# BigLatchingRelay.net
KiCad netlist of a schematic drawn in EAGLE
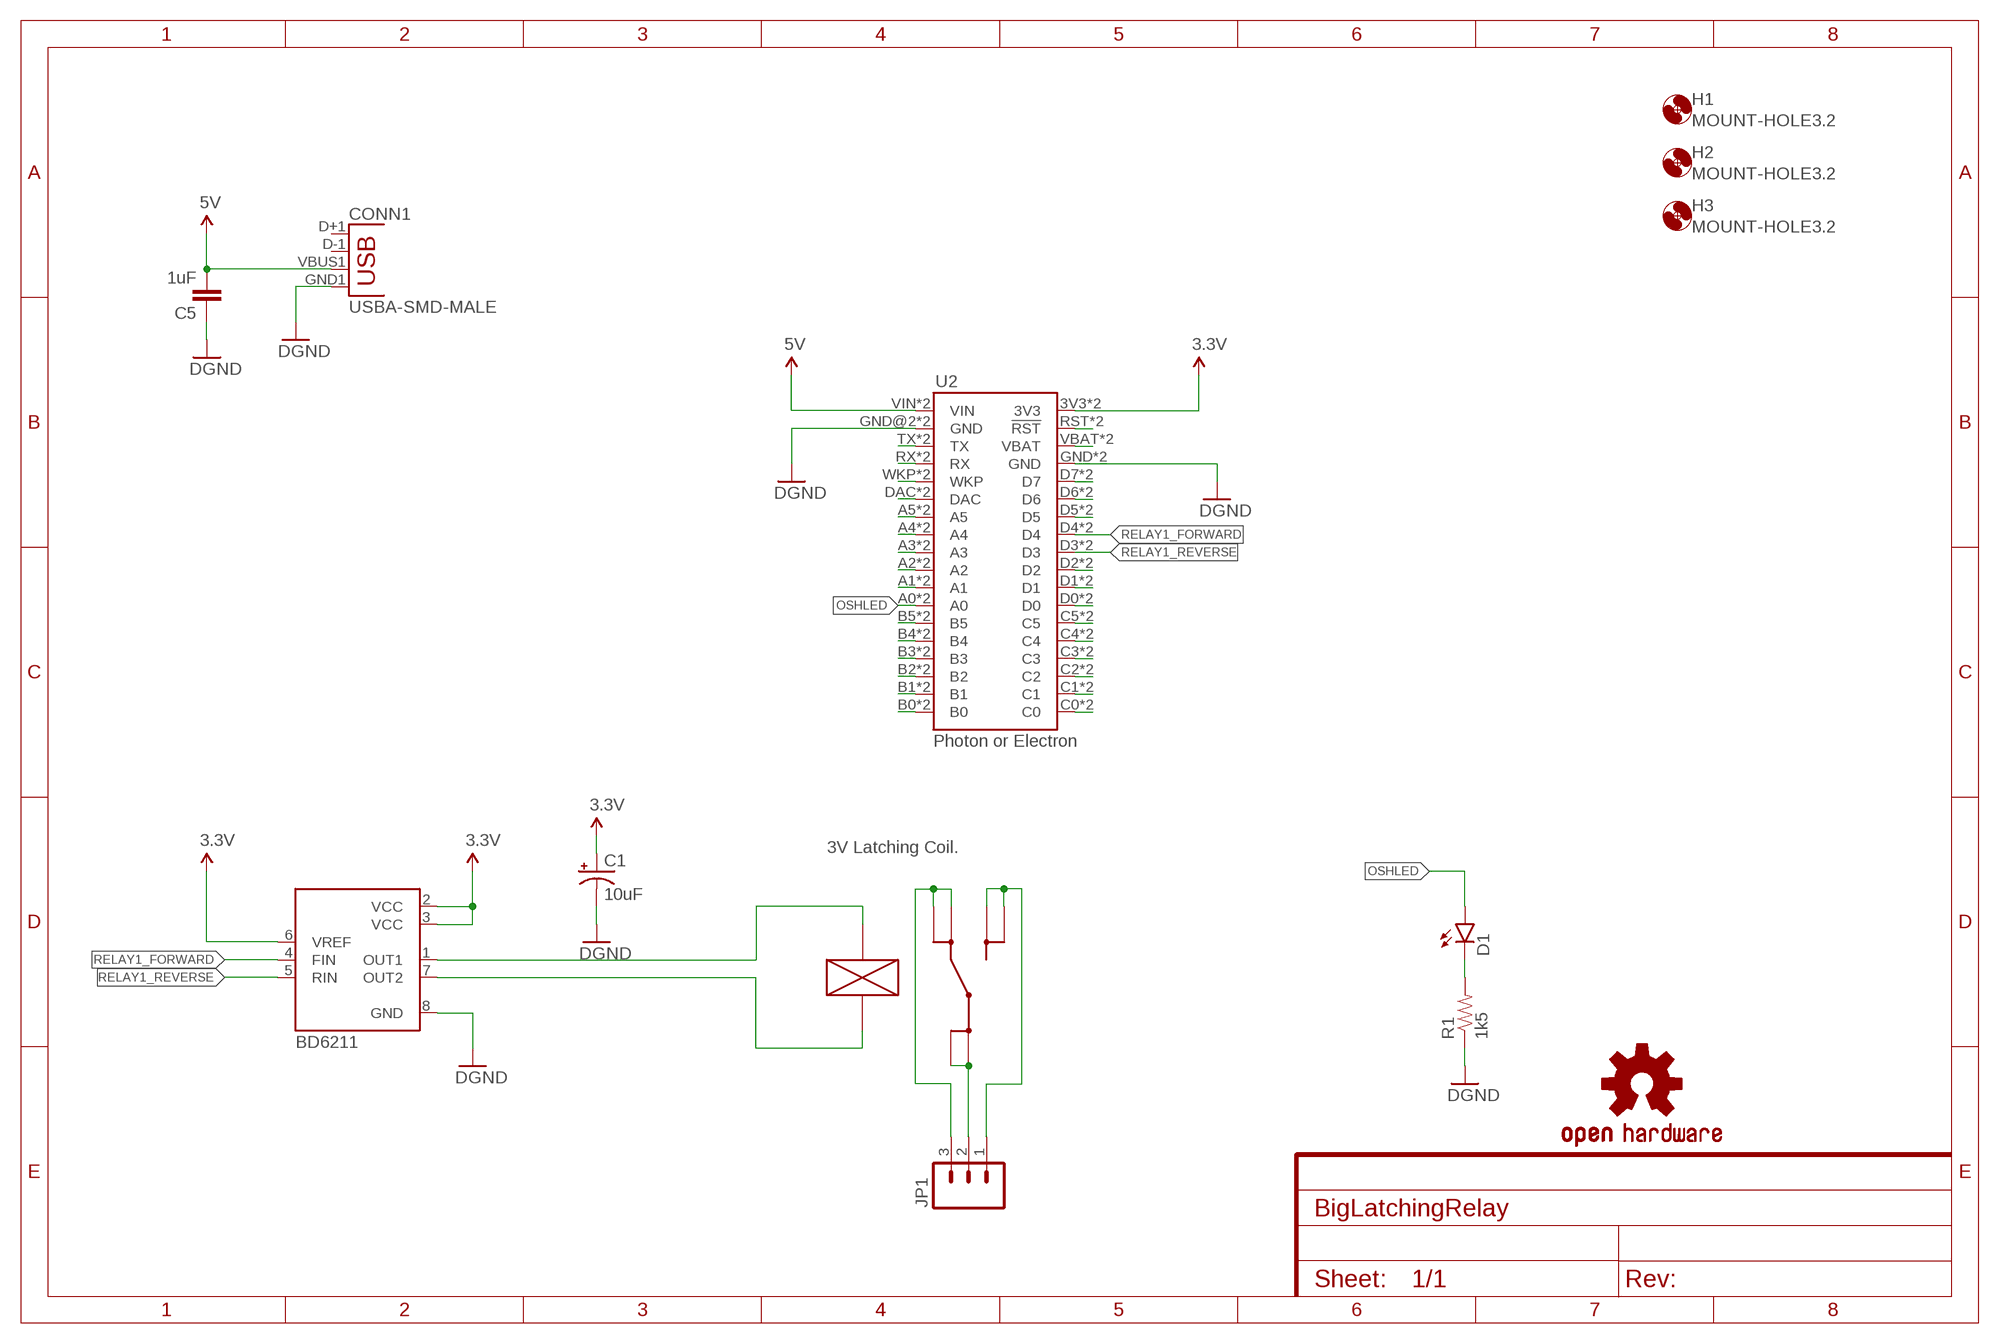
[diagram p0: schematic, sheet 1]

(export (version "E")
  (design (tool "Eeschema 10.0.6"))
  (components
    (comp (ref "C1")
      (value "10uF")
      (footprint "eagle-import:EIA3216")
      (libsource (lib "eagle-import") (part "10UF-16V-10%(TANT)"))
    )
    (comp (ref "C5")
      (value "1uF")
      (footprint "eagle-import:0805")
      (libsource (lib "eagle-import") (part "CAP0805"))
    )
    (comp (ref "CONN1")
      (value "USBA-SMD-MALE")
      (footprint "eagle-import:USB-A-SMT-MALE")
      (libsource (lib "eagle-import") (part "USBA-SMD-MALE"))
    )
    (comp (ref "D1")
      (value "LED1206-BOTTOM")
      (footprint "eagle-import:LED-1206-BOTTOM")
      (libsource (lib "eagle-import") (part "LED1206-BOTTOM"))
    )
    (comp (ref "H1")
      (value "MOUNT-HOLE3.2")
      (footprint "eagle-import:3,2")
      (libsource (lib "eagle-import") (part "MOUNT-HOLE3.2"))
    )
    (comp (ref "H2")
      (value "MOUNT-HOLE3.2")
      (footprint "eagle-import:3,2")
      (libsource (lib "eagle-import") (part "MOUNT-HOLE3.2"))
    )
    (comp (ref "H3")
      (value "MOUNT-HOLE3.2")
      (footprint "eagle-import:3,2")
      (libsource (lib "eagle-import") (part "MOUNT-HOLE3.2"))
    )
    (comp (ref "JP1")
      (value "M03-SCREW-5MM")
      (footprint "eagle-import:SCREWTERMINAL-5MM-3")
      (libsource (lib "eagle-import") (part "M03-SCREW-5MM"))
    )
    (comp (ref "LOGO1")
      (value "OSHW-LOGOM")
      (footprint "eagle-import:OSHW-LOGO-M")
      (libsource (lib "eagle-import") (part "OSHW-LOGOM"))
    )
    (comp (ref "R1")
      (value "1k5")
      (footprint "eagle-import:1206")
      (libsource (lib "eagle-import") (part "RESISTOR1206"))
    )
    (comp (ref "U$1")
      (value "RELAY_G5RL-1E")
      (footprint "eagle-import:G5RL-1E")
      (libsource (lib "eagle-import") (part "RELAY_G5RL-1E"))
    )
    (comp (ref "U2")
      (value "ELECTRONDUALNAMED")
      (footprint "eagle-import:ELECTRON_SIMPLE_SILK_NAMES_DUAL")
      (libsource (lib "eagle-import") (part "ELECTRONDUALNAMED"))
    )
    (comp (ref "U3")
      (value "BD6211F")
      (footprint "eagle-import:SOP8")
      (libsource (lib "eagle-import") (part "BD6211F"))
    )
  )
  (nets
    (net (code "1") (name "3.3V") (class "Default")
      (node (ref "C1") (pin "A") (pinfunction "+_A") (pintype "passive"))
      (node (ref "U2") (pin "3V3") (pinfunction "3V3_3V3") (pintype "power_in"))
      (node (ref "U2") (pin "3V3_1") (pinfunction "3V3_3V3_1") (pintype "power_in"))
      (node (ref "U3") (pin "2") (pinfunction "VCC_2") (pintype "power_in"))
      (node (ref "U3") (pin "3") (pinfunction "VCC_3") (pintype "power_in"))
      (node (ref "U3") (pin "6") (pinfunction "VREF_6") (pintype "passive"))
    )
    (net (code "2") (name "5V") (class "Default")
      (node (ref "C5") (pin "2") (pinfunction "2_2") (pintype "passive"))
      (node (ref "CONN1") (pin "VBUS1") (pinfunction "VBUS_VBUS1") (pintype "bidirectional"))
      (node (ref "U2") (pin "VIN") (pinfunction "VIN_VIN") (pintype "power_in"))
      (node (ref "U2") (pin "VIN_1B") (pinfunction "VIN_VIN_1B") (pintype "power_in"))
    )
    (net (code "3") (name "DGND") (class "Default")
      (node (ref "C1") (pin "C") (pinfunction "-_C") (pintype "passive"))
      (node (ref "C5") (pin "1") (pinfunction "1_1") (pintype "passive"))
      (node (ref "CONN1") (pin "GND1") (pinfunction "GND_GND1") (pintype "bidirectional"))
      (node (ref "R1") (pin "1") (pinfunction "1_1") (pintype "passive"))
      (node (ref "U2") (pin "GND") (pinfunction "GND_GND") (pintype "power_in"))
      (node (ref "U2") (pin "GND@2") (pinfunction "GND_GND@2") (pintype "power_in"))
      (node (ref "U2") (pin "GND_1") (pinfunction "GND_GND_1") (pintype "power_in"))
      (node (ref "U2") (pin "GND_1B") (pinfunction "GND_GND_1B") (pintype "power_in"))
      (node (ref "U3") (pin "8") (pinfunction "GND_8") (pintype "power_in"))
    )
    (net (code "4") (name "Net-(D1-PadC)") (class "Default")
      (node (ref "D1") (pin "C") (pinfunction "C_C") (pintype "passive"))
      (node (ref "R1") (pin "2") (pinfunction "2_2") (pintype "passive"))
    )
    (net (code "5") (name "Net-(JP1-Pad1)") (class "Default")
      (node (ref "JP1") (pin "1") (pinfunction "1_1") (pintype "passive"))
      (node (ref "U$1") (pin "NO@1") (pinfunction "NO_NO@1") (pintype "bidirectional"))
      (node (ref "U$1") (pin "NO@2") (pinfunction "NO_NO@2") (pintype "bidirectional"))
    )
    (net (code "6") (name "Net-(JP1-Pad2)") (class "Default")
      (node (ref "JP1") (pin "2") (pinfunction "2_2") (pintype "passive"))
      (node (ref "U$1") (pin "COM@1") (pinfunction "COM_COM@1") (pintype "bidirectional"))
      (node (ref "U$1") (pin "COM@2") (pinfunction "COM_COM@2") (pintype "bidirectional"))
    )
    (net (code "7") (name "Net-(JP1-Pad3)") (class "Default")
      (node (ref "JP1") (pin "3") (pinfunction "3_3") (pintype "passive"))
      (node (ref "U$1") (pin "NC@1") (pinfunction "NC_NC@1") (pintype "bidirectional"))
      (node (ref "U$1") (pin "NC@2") (pinfunction "NC_NC@2") (pintype "bidirectional"))
    )
    (net (code "8") (name "Net-(U2-A1-PadA1_1)") (class "Default")
      (node (ref "U2") (pin "A1") (pinfunction "A1_A1") (pintype "bidirectional"))
      (node (ref "U2") (pin "A1_1") (pinfunction "A1_A1_1") (pintype "bidirectional"))
    )
    (net (code "9") (name "Net-(U2-A2-PadA2_1)") (class "Default")
      (node (ref "U2") (pin "A2") (pinfunction "A2_A2") (pintype "bidirectional"))
      (node (ref "U2") (pin "A2_1") (pinfunction "A2_A2_1") (pintype "bidirectional"))
    )
    (net (code "10") (name "Net-(U2-A3-PadA3_1)") (class "Default")
      (node (ref "U2") (pin "A3") (pinfunction "A3_A3") (pintype "bidirectional"))
      (node (ref "U2") (pin "A3_1") (pinfunction "A3_A3_1") (pintype "bidirectional"))
    )
    (net (code "11") (name "Net-(U2-A4-PadA4_1)") (class "Default")
      (node (ref "U2") (pin "A4") (pinfunction "A4_A4") (pintype "bidirectional"))
      (node (ref "U2") (pin "A4_1") (pinfunction "A4_A4_1") (pintype "bidirectional"))
    )
    (net (code "12") (name "Net-(U2-A5-PadA5_1)") (class "Default")
      (node (ref "U2") (pin "A5") (pinfunction "A5_A5") (pintype "bidirectional"))
      (node (ref "U2") (pin "A5_1") (pinfunction "A5_A5_1") (pintype "bidirectional"))
    )
    (net (code "13") (name "Net-(U2-B0-PadB0_1)") (class "Default")
      (node (ref "U2") (pin "B0") (pinfunction "B0_B0") (pintype "bidirectional"))
      (node (ref "U2") (pin "B0_1") (pinfunction "B0_B0_1") (pintype "bidirectional"))
    )
    (net (code "14") (name "Net-(U2-B1-PadB1_1)") (class "Default")
      (node (ref "U2") (pin "B1") (pinfunction "B1_B1") (pintype "bidirectional"))
      (node (ref "U2") (pin "B1_1") (pinfunction "B1_B1_1") (pintype "bidirectional"))
    )
    (net (code "15") (name "Net-(U2-B2-PadB2_1)") (class "Default")
      (node (ref "U2") (pin "B2") (pinfunction "B2_B2") (pintype "bidirectional"))
      (node (ref "U2") (pin "B2_1") (pinfunction "B2_B2_1") (pintype "bidirectional"))
    )
    (net (code "16") (name "Net-(U2-B3-PadB3_1)") (class "Default")
      (node (ref "U2") (pin "B3") (pinfunction "B3_B3") (pintype "bidirectional"))
      (node (ref "U2") (pin "B3_1") (pinfunction "B3_B3_1") (pintype "bidirectional"))
    )
    (net (code "17") (name "Net-(U2-B4-PadB4_1)") (class "Default")
      (node (ref "U2") (pin "B4") (pinfunction "B4_B4") (pintype "bidirectional"))
      (node (ref "U2") (pin "B4_1") (pinfunction "B4_B4_1") (pintype "bidirectional"))
    )
    (net (code "18") (name "Net-(U2-B5-PadB5_1)") (class "Default")
      (node (ref "U2") (pin "B5") (pinfunction "B5_B5") (pintype "bidirectional"))
      (node (ref "U2") (pin "B5_1") (pinfunction "B5_B5_1") (pintype "bidirectional"))
    )
    (net (code "19") (name "Net-(U2-C0-PadC0_1)") (class "Default")
      (node (ref "U2") (pin "C0") (pinfunction "C0_C0") (pintype "bidirectional"))
      (node (ref "U2") (pin "C0_1") (pinfunction "C0_C0_1") (pintype "bidirectional"))
    )
    (net (code "20") (name "Net-(U2-C1-PadC1_1)") (class "Default")
      (node (ref "U2") (pin "C1") (pinfunction "C1_C1") (pintype "bidirectional"))
      (node (ref "U2") (pin "C1_1") (pinfunction "C1_C1_1") (pintype "bidirectional"))
    )
    (net (code "21") (name "Net-(U2-C2-PadC2_1)") (class "Default")
      (node (ref "U2") (pin "C2") (pinfunction "C2_C2") (pintype "bidirectional"))
      (node (ref "U2") (pin "C2_1") (pinfunction "C2_C2_1") (pintype "bidirectional"))
    )
    (net (code "22") (name "Net-(U2-C3-PadC3_1)") (class "Default")
      (node (ref "U2") (pin "C3") (pinfunction "C3_C3") (pintype "bidirectional"))
      (node (ref "U2") (pin "C3_1") (pinfunction "C3_C3_1") (pintype "bidirectional"))
    )
    (net (code "23") (name "Net-(U2-C4-PadC4_1)") (class "Default")
      (node (ref "U2") (pin "C4") (pinfunction "C4_C4") (pintype "bidirectional"))
      (node (ref "U2") (pin "C4_1") (pinfunction "C4_C4_1") (pintype "bidirectional"))
    )
    (net (code "24") (name "Net-(U2-C5-PadC5_1)") (class "Default")
      (node (ref "U2") (pin "C5") (pinfunction "C5_C5") (pintype "bidirectional"))
      (node (ref "U2") (pin "C5_1") (pinfunction "C5_C5_1") (pintype "bidirectional"))
    )
    (net (code "25") (name "Net-(U2-D0-PadD0_1)") (class "Default")
      (node (ref "U2") (pin "D0") (pinfunction "D0_D0") (pintype "bidirectional"))
      (node (ref "U2") (pin "D0_1") (pinfunction "D0_D0_1") (pintype "bidirectional"))
    )
    (net (code "26") (name "Net-(U2-D1-PadD1_1)") (class "Default")
      (node (ref "U2") (pin "D1") (pinfunction "D1_D1") (pintype "bidirectional"))
      (node (ref "U2") (pin "D1_1") (pinfunction "D1_D1_1") (pintype "bidirectional"))
    )
    (net (code "27") (name "Net-(U2-D2-PadD2_1)") (class "Default")
      (node (ref "U2") (pin "D2") (pinfunction "D2_D2") (pintype "bidirectional"))
      (node (ref "U2") (pin "D2_1") (pinfunction "D2_D2_1") (pintype "bidirectional"))
    )
    (net (code "28") (name "Net-(U2-D5-PadD5_1)") (class "Default")
      (node (ref "U2") (pin "D5") (pinfunction "D5_D5") (pintype "bidirectional"))
      (node (ref "U2") (pin "D5_1") (pinfunction "D5_D5_1") (pintype "bidirectional"))
    )
    (net (code "29") (name "Net-(U2-D6-PadD6_1)") (class "Default")
      (node (ref "U2") (pin "D6") (pinfunction "D6_D6") (pintype "bidirectional"))
      (node (ref "U2") (pin "D6_1") (pinfunction "D6_D6_1") (pintype "bidirectional"))
    )
    (net (code "30") (name "Net-(U2-D7-PadD7_1)") (class "Default")
      (node (ref "U2") (pin "D7") (pinfunction "D7_D7") (pintype "bidirectional"))
      (node (ref "U2") (pin "D7_1") (pinfunction "D7_D7_1") (pintype "bidirectional"))
    )
    (net (code "31") (name "Net-(U2-DAC-PadDAC_1)") (class "Default")
      (node (ref "U2") (pin "DAC") (pinfunction "DAC_DAC") (pintype "bidirectional"))
      (node (ref "U2") (pin "DAC_1") (pinfunction "DAC_DAC_1") (pintype "bidirectional"))
    )
    (net (code "32") (name "Net-(U2-PadRX)") (class "Default")
      (node (ref "U2") (pin "RX") (pinfunction "RX_RX") (pintype "bidirectional"))
      (node (ref "U2") (pin "RX_1") (pinfunction "RX_RX_1") (pintype "bidirectional"))
    )
    (net (code "33") (name "Net-(U2-PadTX)") (class "Default")
      (node (ref "U2") (pin "TX") (pinfunction "TX_TX") (pintype "bidirectional"))
      (node (ref "U2") (pin "TX_1") (pinfunction "TX_TX_1") (pintype "bidirectional"))
    )
    (net (code "34") (name "Net-(U2-PadVBAT)") (class "Default")
      (node (ref "U2") (pin "VBAT") (pinfunction "VBAT_VBAT") (pintype "passive"))
      (node (ref "U2") (pin "VBATT_1") (pinfunction "VBAT_VBATT_1") (pintype "passive"))
    )
    (net (code "35") (name "Net-(U2-PadWKP)") (class "Default")
      (node (ref "U2") (pin "WKP") (pinfunction "WKP_WKP") (pintype "bidirectional"))
      (node (ref "U2") (pin "WKP_1") (pinfunction "WKP_WKP_1") (pintype "bidirectional"))
    )
    (net (code "36") (name "Net-(U2-~{RST}-PadRST)") (class "Default")
      (node (ref "U2") (pin "RST") (pinfunction "~{RST}_RST") (pintype "bidirectional"))
      (node (ref "U2") (pin "RST_1") (pinfunction "~{RST}_RST_1") (pintype "bidirectional"))
    )
    (net (code "37") (name "Net-(U3-OUT1)") (class "Default")
      (node (ref "U$1") (pin "COIL+") (pinfunction "COIL+_COIL+") (pintype "bidirectional"))
      (node (ref "U3") (pin "1") (pinfunction "OUT1_1") (pintype "output"))
    )
    (net (code "38") (name "Net-(U3-OUT2)") (class "Default")
      (node (ref "U$1") (pin "COIL-") (pinfunction "COIL-_COIL-") (pintype "bidirectional"))
      (node (ref "U3") (pin "7") (pinfunction "OUT2_7") (pintype "output"))
    )
    (net (code "39") (name "OSHLED") (class "Default")
      (node (ref "D1") (pin "A") (pinfunction "A_A") (pintype "passive"))
      (node (ref "U2") (pin "A0") (pinfunction "A0_A0") (pintype "bidirectional"))
      (node (ref "U2") (pin "A0_1") (pinfunction "A0_A0_1") (pintype "bidirectional"))
    )
    (net (code "40") (name "RELAY1_FORWARD") (class "Default")
      (node (ref "U2") (pin "D4") (pinfunction "D4_D4") (pintype "bidirectional"))
      (node (ref "U2") (pin "D4_1") (pinfunction "D4_D4_1") (pintype "bidirectional"))
      (node (ref "U3") (pin "4") (pinfunction "FIN_4") (pintype "input"))
    )
    (net (code "41") (name "RELAY1_REVERSE") (class "Default")
      (node (ref "U2") (pin "D3") (pinfunction "D3_D3") (pintype "bidirectional"))
      (node (ref "U2") (pin "D3_1") (pinfunction "D3_D3_1") (pintype "bidirectional"))
      (node (ref "U3") (pin "5") (pinfunction "RIN_5") (pintype "input"))
    )
    (net (code "42") (name "unconnected-(CONN1-D+-PadD+1)") (class "Default")
      (node (ref "CONN1") (pin "D+1") (pinfunction "D+_D+1") (pintype "bidirectional"))
    )
    (net (code "43") (name "unconnected-(CONN1-D--PadD-1)") (class "Default")
      (node (ref "CONN1") (pin "D-1") (pinfunction "D-_D-1") (pintype "bidirectional"))
    )
  )
)
